# MainBoard.net
KiCad netlist of a schematic drawn in EAGLE
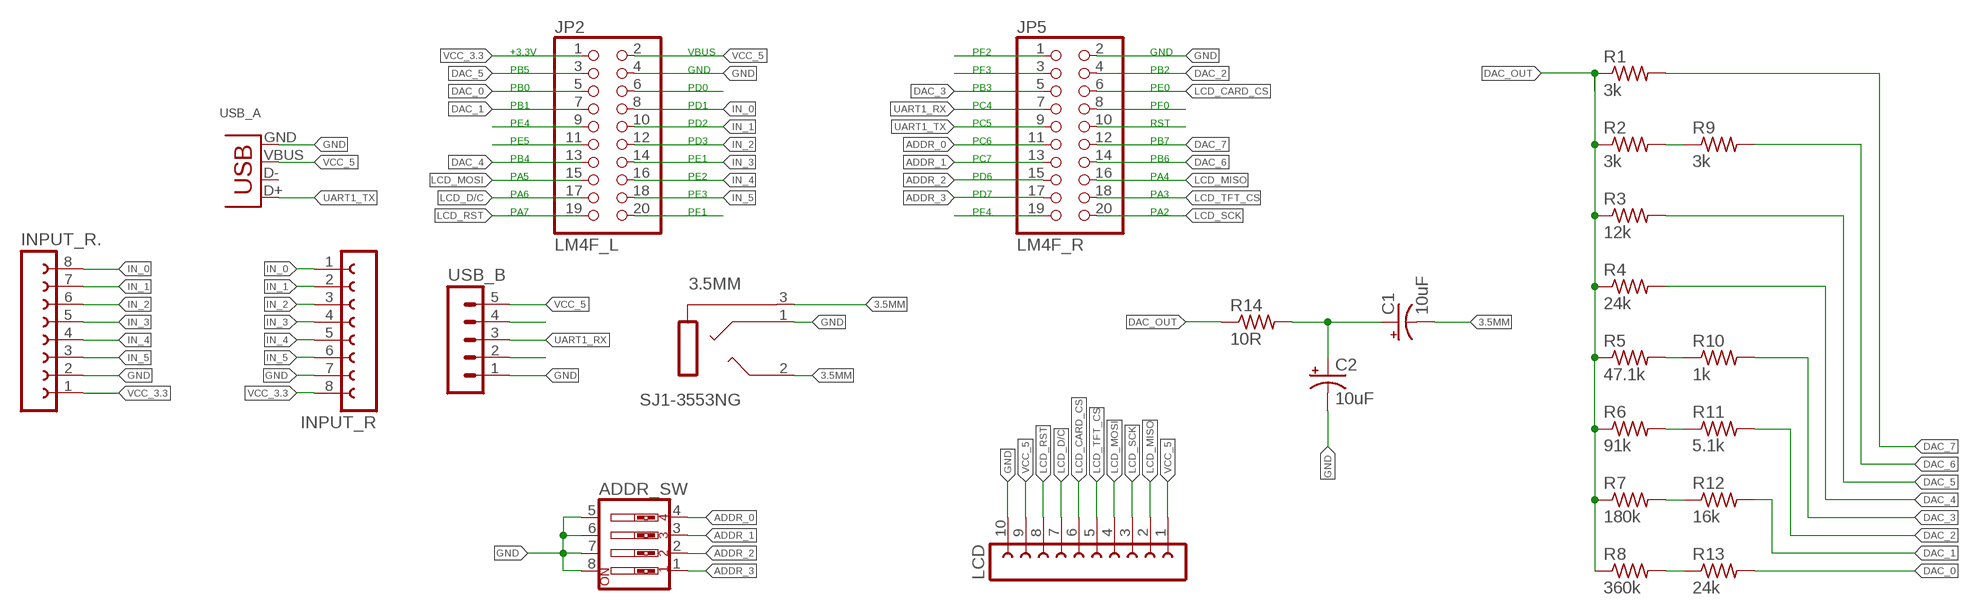
[diagram p0: schematic, sheet 1]

(export (version "E")
  (design (tool "Eeschema 10.0.6"))
  (components
    (comp (ref "3.5MM")
      (value "SJ1-3553NG")
      (footprint "eagle-import:SJ1-3553NG")
      (fields (field (name "DIGI-KEY_PART_NUMBER") "CP1-3553NG-ND") (field (name "MF") "CUI"))
      (libsource (lib "eagle-import") (part "SJ1-3553NG"))
    )
    (comp (ref "ADDR_SW")
      (value "SW_DIP-4")
      (footprint "eagle-import:EDG-04")
      (libsource (lib "eagle-import") (part "SW_DIP-4"))
    )
    (comp (ref "C1")
      (value "10uF")
      (footprint "eagle-import:E2-4")
      (libsource (lib "eagle-import") (part "CPOL-USE2-4"))
    )
    (comp (ref "C2")
      (value "10uF")
      (footprint "eagle-import:E2-4")
      (libsource (lib "eagle-import") (part "CPOL-USE2-4"))
    )
    (comp (ref "INPUT_R")
      (value "FE08W")
      (footprint "eagle-import:FE08W")
      (libsource (lib "eagle-import") (part "FE08W"))
    )
    (comp (ref "INPUT_R.")
      (value "FE08W")
      (footprint "eagle-import:FE08W")
      (libsource (lib "eagle-import") (part "FE08W"))
    )
    (comp (ref "JP2")
      (value "LM4F_L")
      (footprint "eagle-import:2X10")
      (libsource (lib "eagle-import") (part "PINHD-2X10"))
    )
    (comp (ref "JP5")
      (value "LM4F_R")
      (footprint "eagle-import:2X10")
      (libsource (lib "eagle-import") (part "PINHD-2X10"))
    )
    (comp (ref "LCD")
      (value "FE10-1")
      (footprint "eagle-import:FE10")
      (libsource (lib "eagle-import") (part "FE10-1"))
    )
    (comp (ref "R1")
      (value "3k")
      (footprint "eagle-import:0309_10")
      (libsource (lib "eagle-import") (part "R-US_0309/10"))
    )
    (comp (ref "R2")
      (value "3k")
      (footprint "eagle-import:0309_10")
      (libsource (lib "eagle-import") (part "R-US_0309/10"))
    )
    (comp (ref "R3")
      (value "12k")
      (footprint "eagle-import:0309_10")
      (libsource (lib "eagle-import") (part "R-US_0309/10"))
    )
    (comp (ref "R4")
      (value "24k")
      (footprint "eagle-import:0309_10")
      (libsource (lib "eagle-import") (part "R-US_0309/10"))
    )
    (comp (ref "R5")
      (value "47.1k")
      (footprint "eagle-import:0309_10")
      (libsource (lib "eagle-import") (part "R-US_0309/10"))
    )
    (comp (ref "R6")
      (value "91k")
      (footprint "eagle-import:0309_10")
      (libsource (lib "eagle-import") (part "R-US_0309/10"))
    )
    (comp (ref "R7")
      (value "180k")
      (footprint "eagle-import:0309_10")
      (libsource (lib "eagle-import") (part "R-US_0309/10"))
    )
    (comp (ref "R8")
      (value "360k")
      (footprint "eagle-import:0309_10")
      (libsource (lib "eagle-import") (part "R-US_0309/10"))
    )
    (comp (ref "R9")
      (value "3k")
      (footprint "eagle-import:0309_10")
      (libsource (lib "eagle-import") (part "R-US_0309/10"))
    )
    (comp (ref "R10")
      (value "1k")
      (footprint "eagle-import:0309_10")
      (libsource (lib "eagle-import") (part "R-US_0309/10"))
    )
    (comp (ref "R11")
      (value "5.1k")
      (footprint "eagle-import:0309_10")
      (libsource (lib "eagle-import") (part "R-US_0309/10"))
    )
    (comp (ref "R12")
      (value "16k")
      (footprint "eagle-import:0309_10")
      (libsource (lib "eagle-import") (part "R-US_0309/10"))
    )
    (comp (ref "R13")
      (value "24k")
      (footprint "eagle-import:0309_10")
      (libsource (lib "eagle-import") (part "R-US_0309/10"))
    )
    (comp (ref "R14")
      (value "10R")
      (footprint "eagle-import:0309_10")
      (libsource (lib "eagle-import") (part "R-US_0309/10"))
    )
    (comp (ref "USB_A")
      (value "USB-A-H")
      (footprint "eagle-import:USB-A-H")
      (libsource (lib "eagle-import") (part "USB-A-H"))
    )
    (comp (ref "USB_B")
      (value "MA05-1")
      (footprint "eagle-import:MA05-1")
      (libsource (lib "eagle-import") (part "MA05-1"))
    )
  )
  (nets
    (net (code "1") (name "3.5MM") (class "Default")
      (node (ref "3.5MM") (pin "2") (pinfunction "TIP_2") (pintype "passive"))
      (node (ref "3.5MM") (pin "3") (pinfunction "SLEEVE_3") (pintype "passive"))
      (node (ref "C1") (pin "-") (pinfunction "-_-") (pintype "passive"))
    )
    (net (code "2") (name "ADDR_0") (class "Default")
      (node (ref "ADDR_SW") (pin "4") (pinfunction "4_4") (pintype "passive"))
      (node (ref "JP5") (pin "11") (pinfunction "11_11") (pintype "passive"))
    )
    (net (code "3") (name "ADDR_1") (class "Default")
      (node (ref "ADDR_SW") (pin "3") (pinfunction "3_3") (pintype "passive"))
      (node (ref "JP5") (pin "13") (pinfunction "13_13") (pintype "passive"))
    )
    (net (code "4") (name "ADDR_2") (class "Default")
      (node (ref "ADDR_SW") (pin "2") (pinfunction "2_2") (pintype "passive"))
      (node (ref "JP5") (pin "15") (pinfunction "15_15") (pintype "passive"))
    )
    (net (code "5") (name "ADDR_3") (class "Default")
      (node (ref "ADDR_SW") (pin "1") (pinfunction "1_1") (pintype "passive"))
      (node (ref "JP5") (pin "17") (pinfunction "17_17") (pintype "passive"))
    )
    (net (code "6") (name "DAC_0") (class "Default")
      (node (ref "JP2") (pin "5") (pinfunction "5_5") (pintype "passive"))
      (node (ref "R13") (pin "2") (pinfunction "2_2") (pintype "passive"))
    )
    (net (code "7") (name "DAC_1") (class "Default")
      (node (ref "JP2") (pin "7") (pinfunction "7_7") (pintype "passive"))
      (node (ref "R12") (pin "2") (pinfunction "2_2") (pintype "passive"))
    )
    (net (code "8") (name "DAC_2") (class "Default")
      (node (ref "JP5") (pin "4") (pinfunction "4_4") (pintype "passive"))
      (node (ref "R11") (pin "2") (pinfunction "2_2") (pintype "passive"))
    )
    (net (code "9") (name "DAC_3") (class "Default")
      (node (ref "JP5") (pin "5") (pinfunction "5_5") (pintype "passive"))
      (node (ref "R10") (pin "2") (pinfunction "2_2") (pintype "passive"))
    )
    (net (code "10") (name "DAC_4") (class "Default")
      (node (ref "JP2") (pin "13") (pinfunction "13_13") (pintype "passive"))
      (node (ref "R4") (pin "2") (pinfunction "2_2") (pintype "passive"))
    )
    (net (code "11") (name "DAC_5") (class "Default")
      (node (ref "JP2") (pin "3") (pinfunction "3_3") (pintype "passive"))
      (node (ref "R3") (pin "2") (pinfunction "2_2") (pintype "passive"))
    )
    (net (code "12") (name "DAC_6") (class "Default")
      (node (ref "JP5") (pin "14") (pinfunction "14_14") (pintype "passive"))
      (node (ref "R9") (pin "2") (pinfunction "2_2") (pintype "passive"))
    )
    (net (code "13") (name "DAC_7") (class "Default")
      (node (ref "JP5") (pin "12") (pinfunction "12_12") (pintype "passive"))
      (node (ref "R1") (pin "2") (pinfunction "2_2") (pintype "passive"))
    )
    (net (code "14") (name "DAC_OUT") (class "Default")
      (node (ref "R1") (pin "1") (pinfunction "1_1") (pintype "passive"))
      (node (ref "R14") (pin "1") (pinfunction "1_1") (pintype "passive"))
      (node (ref "R2") (pin "1") (pinfunction "1_1") (pintype "passive"))
      (node (ref "R3") (pin "1") (pinfunction "1_1") (pintype "passive"))
      (node (ref "R4") (pin "1") (pinfunction "1_1") (pintype "passive"))
      (node (ref "R5") (pin "1") (pinfunction "1_1") (pintype "passive"))
      (node (ref "R6") (pin "1") (pinfunction "1_1") (pintype "passive"))
      (node (ref "R7") (pin "1") (pinfunction "1_1") (pintype "passive"))
      (node (ref "R8") (pin "1") (pinfunction "1_1") (pintype "passive"))
    )
    (net (code "15") (name "GND") (class "Default")
      (node (ref "3.5MM") (pin "1") (pinfunction "RING_1") (pintype "passive"))
      (node (ref "ADDR_SW") (pin "5") (pinfunction "5_5") (pintype "passive"))
      (node (ref "ADDR_SW") (pin "6") (pinfunction "6_6") (pintype "passive"))
      (node (ref "ADDR_SW") (pin "7") (pinfunction "7_7") (pintype "passive"))
      (node (ref "ADDR_SW") (pin "8") (pinfunction "8_8") (pintype "passive"))
      (node (ref "C2") (pin "-") (pinfunction "-_-") (pintype "passive"))
      (node (ref "INPUT_R") (pin "7") (pinfunction "7_7") (pintype "passive"))
      (node (ref "INPUT_R.") (pin "2") (pinfunction "2_2") (pintype "passive"))
      (node (ref "JP2") (pin "4") (pinfunction "4_4") (pintype "passive"))
      (node (ref "JP5") (pin "2") (pinfunction "2_2") (pintype "passive"))
      (node (ref "LCD") (pin "10") (pinfunction "10_10") (pintype "passive"))
      (node (ref "USB_A") (pin "GND") (pinfunction "GND_GND") (pintype "bidirectional"))
      (node (ref "USB_B") (pin "1") (pinfunction "1_1") (pintype "passive"))
    )
    (net (code "16") (name "IN_0") (class "Default")
      (node (ref "INPUT_R") (pin "1") (pinfunction "1_1") (pintype "passive"))
      (node (ref "INPUT_R.") (pin "8") (pinfunction "8_8") (pintype "passive"))
      (node (ref "JP2") (pin "8") (pinfunction "8_8") (pintype "passive"))
    )
    (net (code "17") (name "IN_1") (class "Default")
      (node (ref "INPUT_R") (pin "2") (pinfunction "2_2") (pintype "passive"))
      (node (ref "INPUT_R.") (pin "7") (pinfunction "7_7") (pintype "passive"))
      (node (ref "JP2") (pin "10") (pinfunction "10_10") (pintype "passive"))
    )
    (net (code "18") (name "IN_2") (class "Default")
      (node (ref "INPUT_R") (pin "3") (pinfunction "3_3") (pintype "passive"))
      (node (ref "INPUT_R.") (pin "6") (pinfunction "6_6") (pintype "passive"))
      (node (ref "JP2") (pin "12") (pinfunction "12_12") (pintype "passive"))
    )
    (net (code "19") (name "IN_3") (class "Default")
      (node (ref "INPUT_R") (pin "4") (pinfunction "4_4") (pintype "passive"))
      (node (ref "INPUT_R.") (pin "5") (pinfunction "5_5") (pintype "passive"))
      (node (ref "JP2") (pin "14") (pinfunction "14_14") (pintype "passive"))
    )
    (net (code "20") (name "IN_4") (class "Default")
      (node (ref "INPUT_R") (pin "5") (pinfunction "5_5") (pintype "passive"))
      (node (ref "INPUT_R.") (pin "4") (pinfunction "4_4") (pintype "passive"))
      (node (ref "JP2") (pin "16") (pinfunction "16_16") (pintype "passive"))
    )
    (net (code "21") (name "IN_5") (class "Default")
      (node (ref "INPUT_R") (pin "6") (pinfunction "6_6") (pintype "passive"))
      (node (ref "INPUT_R.") (pin "3") (pinfunction "3_3") (pintype "passive"))
      (node (ref "JP2") (pin "18") (pinfunction "18_18") (pintype "passive"))
    )
    (net (code "22") (name "LCD_CARD_CS") (class "Default")
      (node (ref "JP5") (pin "6") (pinfunction "6_6") (pintype "passive"))
      (node (ref "LCD") (pin "6") (pinfunction "6_6") (pintype "passive"))
    )
    (net (code "23") (name "LCD_D{slash}C") (class "Default")
      (node (ref "JP2") (pin "17") (pinfunction "17_17") (pintype "passive"))
      (node (ref "LCD") (pin "7") (pinfunction "7_7") (pintype "passive"))
    )
    (net (code "24") (name "LCD_MISO") (class "Default")
      (node (ref "JP5") (pin "16") (pinfunction "16_16") (pintype "passive"))
      (node (ref "LCD") (pin "2") (pinfunction "2_2") (pintype "passive"))
    )
    (net (code "25") (name "LCD_MOSI") (class "Default")
      (node (ref "JP2") (pin "15") (pinfunction "15_15") (pintype "passive"))
      (node (ref "LCD") (pin "4") (pinfunction "4_4") (pintype "passive"))
    )
    (net (code "26") (name "LCD_RST") (class "Default")
      (node (ref "JP2") (pin "19") (pinfunction "19_19") (pintype "passive"))
      (node (ref "LCD") (pin "8") (pinfunction "8_8") (pintype "passive"))
    )
    (net (code "27") (name "LCD_SCK") (class "Default")
      (node (ref "JP5") (pin "20") (pinfunction "20_20") (pintype "passive"))
      (node (ref "LCD") (pin "3") (pinfunction "3_3") (pintype "passive"))
    )
    (net (code "28") (name "LCD_TFT_CS") (class "Default")
      (node (ref "JP5") (pin "18") (pinfunction "18_18") (pintype "passive"))
      (node (ref "LCD") (pin "5") (pinfunction "5_5") (pintype "passive"))
    )
    (net (code "29") (name "Net-(C1-Pad+)") (class "Default")
      (node (ref "C1") (pin "+") (pinfunction "+_+") (pintype "passive"))
      (node (ref "C2") (pin "+") (pinfunction "+_+") (pintype "passive"))
      (node (ref "R14") (pin "2") (pinfunction "2_2") (pintype "passive"))
    )
    (net (code "30") (name "Net-(R2-Pad2)") (class "Default")
      (node (ref "R2") (pin "2") (pinfunction "2_2") (pintype "passive"))
      (node (ref "R9") (pin "1") (pinfunction "1_1") (pintype "passive"))
    )
    (net (code "31") (name "Net-(R10-Pad1)") (class "Default")
      (node (ref "R10") (pin "1") (pinfunction "1_1") (pintype "passive"))
      (node (ref "R5") (pin "2") (pinfunction "2_2") (pintype "passive"))
    )
    (net (code "32") (name "Net-(R11-Pad1)") (class "Default")
      (node (ref "R11") (pin "1") (pinfunction "1_1") (pintype "passive"))
      (node (ref "R6") (pin "2") (pinfunction "2_2") (pintype "passive"))
    )
    (net (code "33") (name "Net-(R12-Pad1)") (class "Default")
      (node (ref "R12") (pin "1") (pinfunction "1_1") (pintype "passive"))
      (node (ref "R7") (pin "2") (pinfunction "2_2") (pintype "passive"))
    )
    (net (code "34") (name "Net-(R13-Pad1)") (class "Default")
      (node (ref "R13") (pin "1") (pinfunction "1_1") (pintype "passive"))
      (node (ref "R8") (pin "2") (pinfunction "2_2") (pintype "passive"))
    )
    (net (code "35") (name "UART1_RX") (class "Default")
      (node (ref "JP5") (pin "7") (pinfunction "7_7") (pintype "passive"))
      (node (ref "USB_B") (pin "3") (pinfunction "3_3") (pintype "passive"))
    )
    (net (code "36") (name "UART1_TX") (class "Default")
      (node (ref "JP5") (pin "9") (pinfunction "9_9") (pintype "passive"))
      (node (ref "USB_A") (pin "D+") (pinfunction "D+_D+") (pintype "bidirectional"))
    )
    (net (code "37") (name "VCC_3.3") (class "Default")
      (node (ref "INPUT_R") (pin "8") (pinfunction "8_8") (pintype "passive"))
      (node (ref "INPUT_R.") (pin "1") (pinfunction "1_1") (pintype "passive"))
      (node (ref "JP2") (pin "1") (pinfunction "1_1") (pintype "passive"))
    )
    (net (code "38") (name "VCC_5") (class "Default")
      (node (ref "JP2") (pin "2") (pinfunction "2_2") (pintype "passive"))
      (node (ref "LCD") (pin "1") (pinfunction "1_1") (pintype "passive"))
      (node (ref "LCD") (pin "9") (pinfunction "9_9") (pintype "passive"))
      (node (ref "USB_A") (pin "VBUS") (pinfunction "VBUS_VBUS") (pintype "bidirectional"))
      (node (ref "USB_B") (pin "5") (pinfunction "5_5") (pintype "passive"))
    )
    (net (code "39") (name "unconnected-(JP2-Pad6)") (class "Default")
      (node (ref "JP2") (pin "6") (pinfunction "6_6") (pintype "passive"))
    )
    (net (code "40") (name "unconnected-(JP2-Pad9)") (class "Default")
      (node (ref "JP2") (pin "9") (pinfunction "9_9") (pintype "passive"))
    )
    (net (code "41") (name "unconnected-(JP2-Pad11)") (class "Default")
      (node (ref "JP2") (pin "11") (pinfunction "11_11") (pintype "passive"))
    )
    (net (code "42") (name "unconnected-(JP2-Pad20)") (class "Default")
      (node (ref "JP2") (pin "20") (pinfunction "20_20") (pintype "passive"))
    )
    (net (code "43") (name "unconnected-(JP5-Pad1)") (class "Default")
      (node (ref "JP5") (pin "1") (pinfunction "1_1") (pintype "passive"))
    )
    (net (code "44") (name "unconnected-(JP5-Pad3)") (class "Default")
      (node (ref "JP5") (pin "3") (pinfunction "3_3") (pintype "passive"))
    )
    (net (code "45") (name "unconnected-(JP5-Pad8)") (class "Default")
      (node (ref "JP5") (pin "8") (pinfunction "8_8") (pintype "passive"))
    )
    (net (code "46") (name "unconnected-(JP5-Pad10)") (class "Default")
      (node (ref "JP5") (pin "10") (pinfunction "10_10") (pintype "passive"))
    )
    (net (code "47") (name "unconnected-(JP5-Pad19)") (class "Default")
      (node (ref "JP5") (pin "19") (pinfunction "19_19") (pintype "passive"))
    )
    (net (code "48") (name "unconnected-(USB_A-PadD-)") (class "Default")
      (node (ref "USB_A") (pin "D-") (pinfunction "D-_D-") (pintype "bidirectional"))
    )
    (net (code "49") (name "unconnected-(USB_B-Pad2)") (class "Default")
      (node (ref "USB_B") (pin "2") (pinfunction "2_2") (pintype "passive"))
    )
    (net (code "50") (name "unconnected-(USB_B-Pad4)") (class "Default")
      (node (ref "USB_B") (pin "4") (pinfunction "4_4") (pintype "passive"))
    )
  )
)
